# m2201-stereo-input.net
KiCad netlist of a schematic drawn in EAGLE
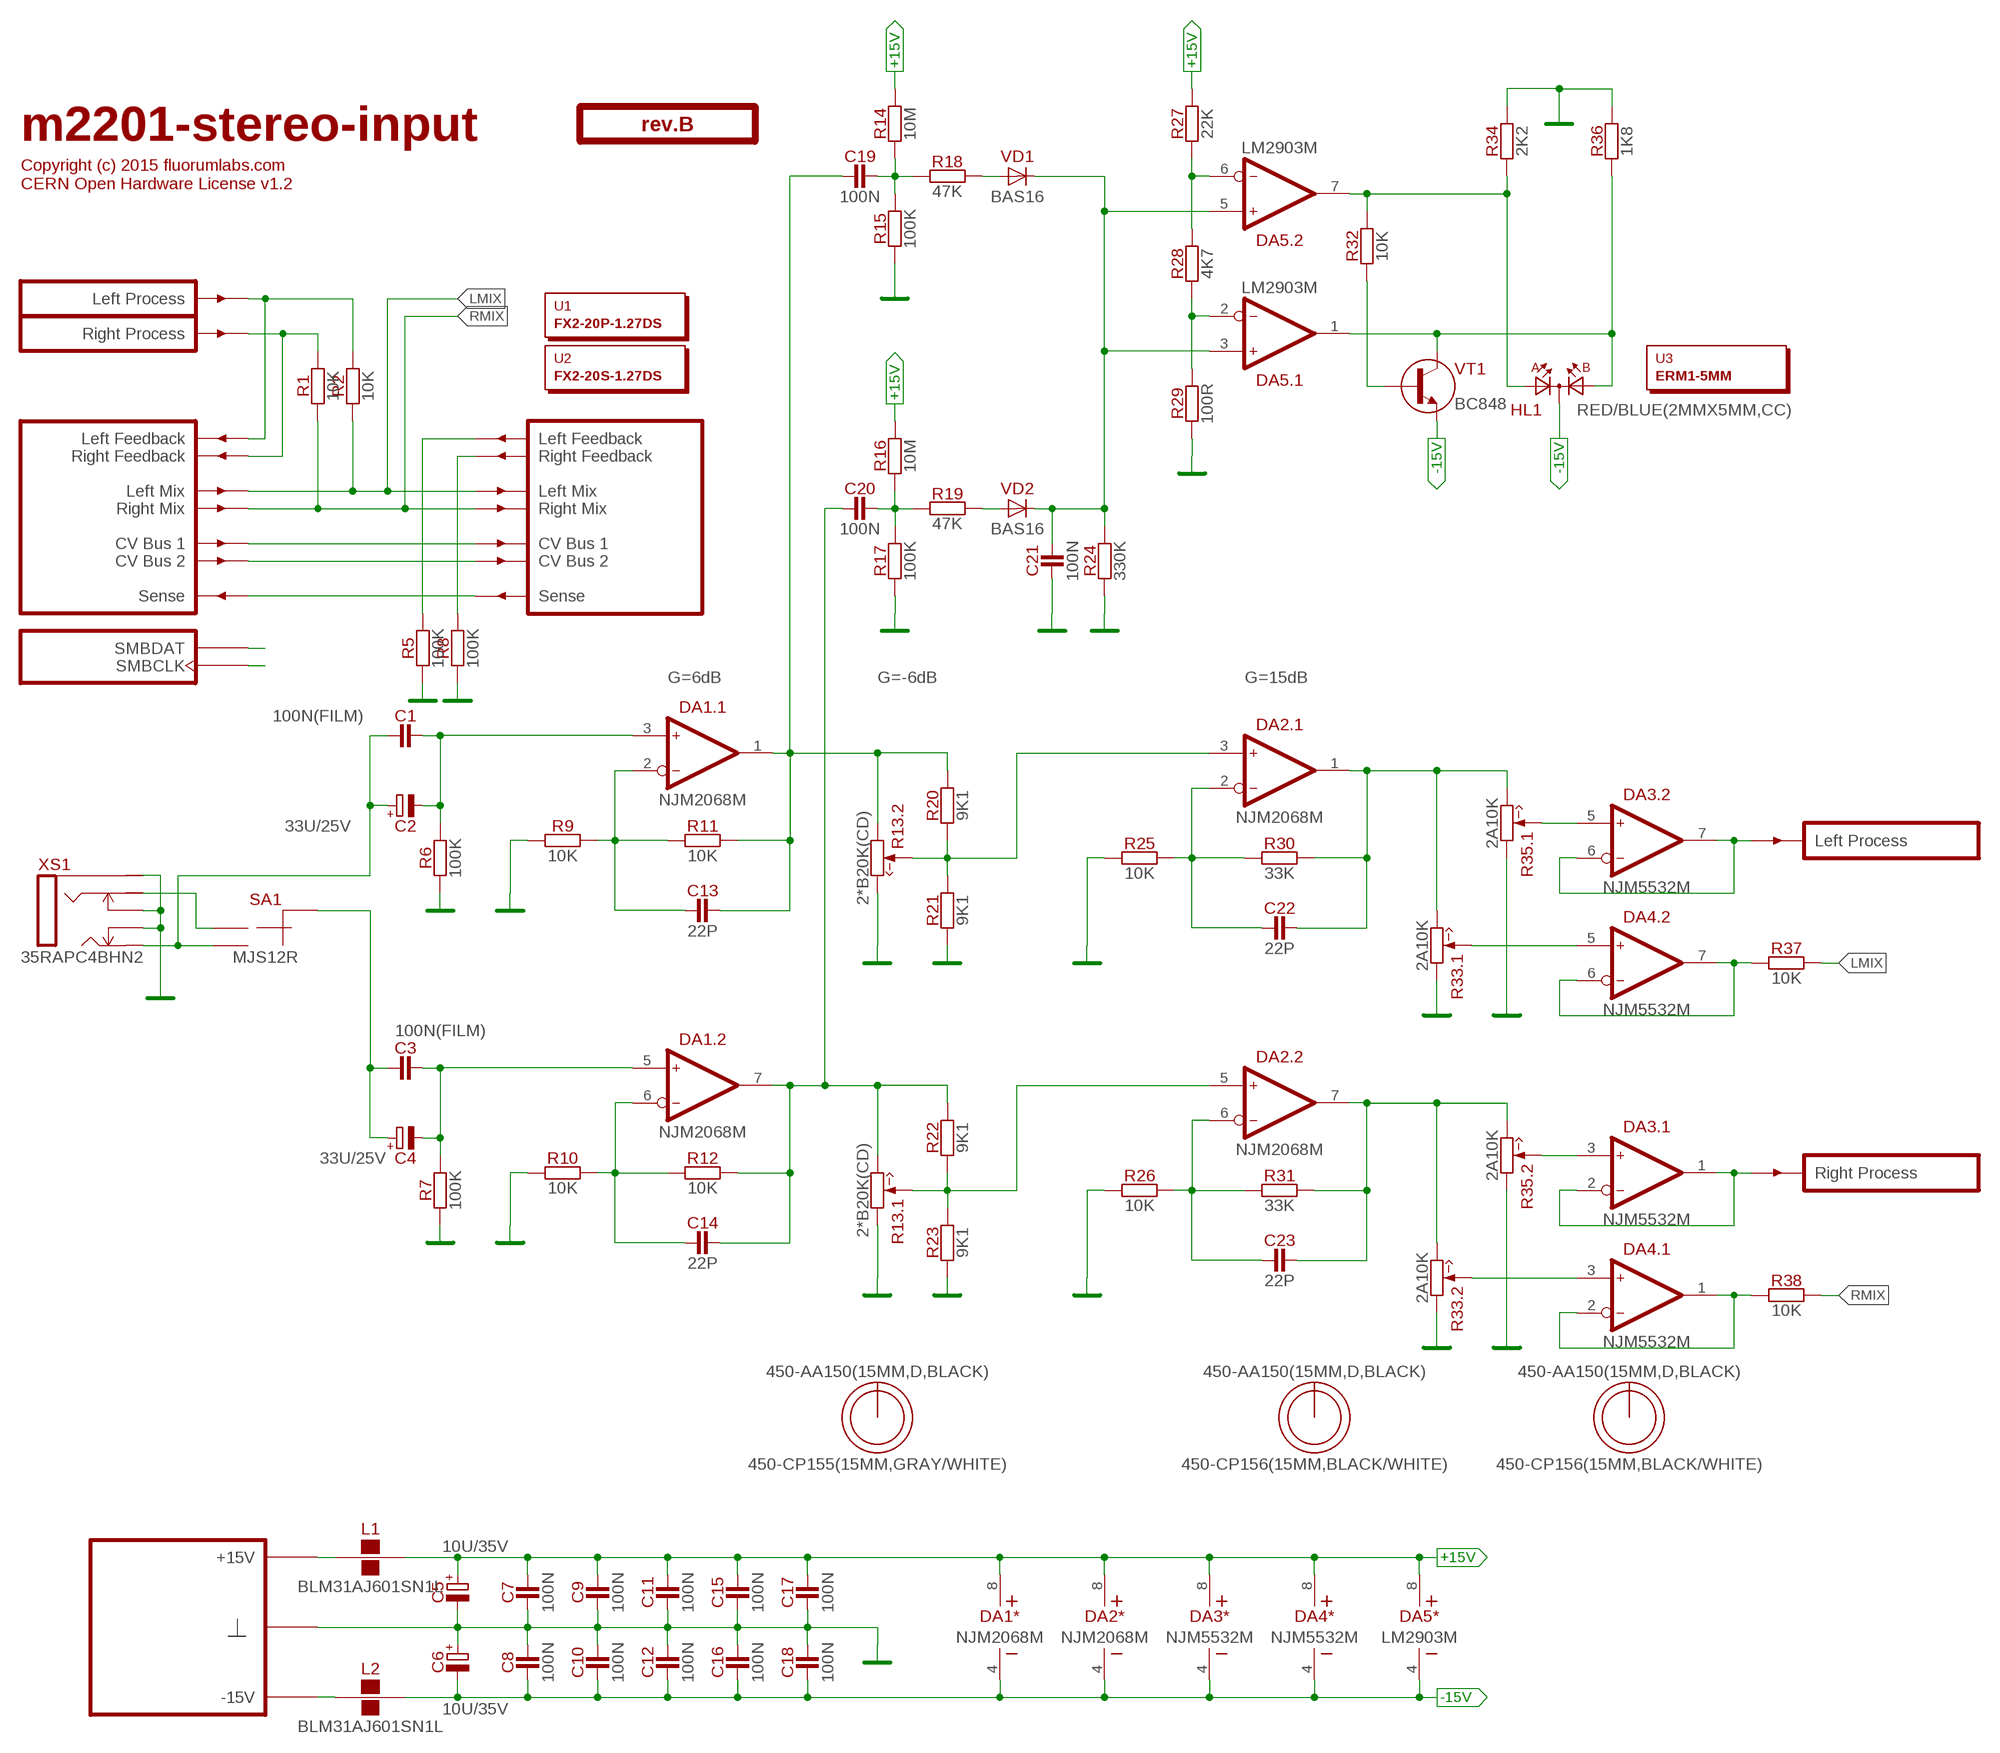
[diagram p0: schematic, sheet 1]

(export (version "E")
  (design (tool "Eeschema 10.0.6"))
  (components
    (comp (ref "C1")
      (value "100N(FILM)")
      (footprint "eagle-import:C050-025X075")
      (libsource (lib "eagle-import") (part "?100N(FILM)"))
    )
    (comp (ref "C2")
      (value "33U/25V")
      (footprint "eagle-import:E2,5-7")
      (libsource (lib "eagle-import") (part "?33U/25V"))
    )
    (comp (ref "C3")
      (value "100N(FILM)")
      (footprint "eagle-import:C050-025X075")
      (libsource (lib "eagle-import") (part "?100N(FILM)"))
    )
    (comp (ref "C4")
      (value "33U/25V")
      (footprint "eagle-import:E2,5-7")
      (libsource (lib "eagle-import") (part "?33U/25V"))
    )
    (comp (ref "C5")
      (value "10U/35V")
      (footprint "eagle-import:E2-5")
      (libsource (lib "eagle-import") (part "?10U/35V"))
    )
    (comp (ref "C6")
      (value "10U/35V")
      (footprint "eagle-import:E2-5")
      (libsource (lib "eagle-import") (part "?10U/35V"))
    )
    (comp (ref "C7")
      (value "100N")
      (footprint "eagle-import:C-0805")
      (libsource (lib "eagle-import") (part "?100N"))
    )
    (comp (ref "C8")
      (value "100N")
      (footprint "eagle-import:C-0805")
      (libsource (lib "eagle-import") (part "?100N"))
    )
    (comp (ref "C9")
      (value "100N")
      (footprint "eagle-import:C-0805")
      (libsource (lib "eagle-import") (part "?100N"))
    )
    (comp (ref "C10")
      (value "100N")
      (footprint "eagle-import:C-0805")
      (libsource (lib "eagle-import") (part "?100N"))
    )
    (comp (ref "C11")
      (value "100N")
      (footprint "eagle-import:C-0805")
      (libsource (lib "eagle-import") (part "?100N"))
    )
    (comp (ref "C12")
      (value "100N")
      (footprint "eagle-import:C-0805")
      (libsource (lib "eagle-import") (part "?100N"))
    )
    (comp (ref "C13")
      (value "22P")
      (footprint "eagle-import:C-0805")
      (libsource (lib "eagle-import") (part "?22P"))
    )
    (comp (ref "C14")
      (value "22P")
      (footprint "eagle-import:C-0805")
      (libsource (lib "eagle-import") (part "?22P"))
    )
    (comp (ref "C15")
      (value "100N")
      (footprint "eagle-import:C-0805")
      (libsource (lib "eagle-import") (part "?100N"))
    )
    (comp (ref "C16")
      (value "100N")
      (footprint "eagle-import:C-0805")
      (libsource (lib "eagle-import") (part "?100N"))
    )
    (comp (ref "C17")
      (value "100N")
      (footprint "eagle-import:C-0805")
      (libsource (lib "eagle-import") (part "?100N"))
    )
    (comp (ref "C18")
      (value "100N")
      (footprint "eagle-import:C-0805")
      (libsource (lib "eagle-import") (part "?100N"))
    )
    (comp (ref "C19")
      (value "100N")
      (footprint "eagle-import:C-0805")
      (libsource (lib "eagle-import") (part "?100N"))
    )
    (comp (ref "C20")
      (value "100N")
      (footprint "eagle-import:C-0805")
      (libsource (lib "eagle-import") (part "?100N"))
    )
    (comp (ref "C21")
      (value "100N")
      (footprint "eagle-import:C-0805")
      (libsource (lib "eagle-import") (part "?100N"))
    )
    (comp (ref "C22")
      (value "22P")
      (footprint "eagle-import:C-0805")
      (libsource (lib "eagle-import") (part "?22P"))
    )
    (comp (ref "C23")
      (value "22P")
      (footprint "eagle-import:C-0805")
      (libsource (lib "eagle-import") (part "?22P"))
    )
    (comp (ref "DA1")
      (value "NJM2068M")
      (footprint "eagle-import:SO-8")
      (libsource (lib "eagle-import") (part "NJM2068M"))
    )
    (comp (ref "DA2")
      (value "NJM2068M")
      (footprint "eagle-import:SO-8")
      (libsource (lib "eagle-import") (part "NJM2068M"))
    )
    (comp (ref "DA3")
      (value "NJM5532M")
      (footprint "eagle-import:SO-8")
      (libsource (lib "eagle-import") (part "NJM5532M"))
    )
    (comp (ref "DA4")
      (value "NJM5532M")
      (footprint "eagle-import:SO-8")
      (libsource (lib "eagle-import") (part "NJM5532M"))
    )
    (comp (ref "DA5")
      (value "LM2903M")
      (footprint "eagle-import:SO-8")
      (libsource (lib "eagle-import") (part "LM2903M"))
    )
    (comp (ref "HL1")
      (value "RED/BLUE(2MMX5MM,CC)")
      (footprint "eagle-import:LED2X5-3PIN")
      (libsource (lib "eagle-import") (part "?(2MMX5MM,CC)RED/BLUE"))
    )
    (comp (ref "L1")
      (value "BLM31AJ601SN1L")
      (footprint "eagle-import:1206")
      (libsource (lib "eagle-import") (part "BLM31AJ601SN1L"))
    )
    (comp (ref "L2")
      (value "BLM31AJ601SN1L")
      (footprint "eagle-import:1206")
      (libsource (lib "eagle-import") (part "BLM31AJ601SN1L"))
    )
    (comp (ref "O1")
      (value "TITLE")
      (footprint "eagle-import:EMPTY")
      (libsource (lib "eagle-import") (part "TITLE"))
    )
    (comp (ref "O2")
      (value "450-AA150(15MM,D,BLACK)")
      (footprint "eagle-import:EMPTY")
      (libsource (lib "eagle-import") (part "450-AA?150(15MM,D,BLACK)"))
    )
    (comp (ref "O3")
      (value "450-CP155(15MM,GRAY/WHITE)")
      (footprint "eagle-import:EMPTY")
      (libsource (lib "eagle-import") (part "450-C?P155(15MM,GRAY/WHITE)"))
    )
    (comp (ref "O4")
      (value "450-AA150(15MM,D,BLACK)")
      (footprint "eagle-import:EMPTY")
      (libsource (lib "eagle-import") (part "450-AA?150(15MM,D,BLACK)"))
    )
    (comp (ref "O5")
      (value "450-CP156(15MM,BLACK/WHITE)")
      (footprint "eagle-import:EMPTY")
      (libsource (lib "eagle-import") (part "450-C?P156(15MM,BLACK/WHITE)"))
    )
    (comp (ref "O6")
      (value "450-AA150(15MM,D,BLACK)")
      (footprint "eagle-import:EMPTY")
      (libsource (lib "eagle-import") (part "450-AA?150(15MM,D,BLACK)"))
    )
    (comp (ref "O7")
      (value "450-CP156(15MM,BLACK/WHITE)")
      (footprint "eagle-import:EMPTY")
      (libsource (lib "eagle-import") (part "450-C?P156(15MM,BLACK/WHITE)"))
    )
    (comp (ref "PCB1")
      (value "rev.B")
      (footprint "eagle-import:ST2-BOARD-50")
      (libsource (lib "eagle-import") (part "ST2-BOARD-50"))
    )
    (comp (ref "R1")
      (value "10K")
      (footprint "eagle-import:R-0805")
      (libsource (lib "eagle-import") (part "?10K"))
    )
    (comp (ref "R2")
      (value "10K")
      (footprint "eagle-import:R-0805")
      (libsource (lib "eagle-import") (part "?10K"))
    )
    (comp (ref "R5")
      (value "100K")
      (footprint "eagle-import:R-0805")
      (libsource (lib "eagle-import") (part "?100K"))
    )
    (comp (ref "R6")
      (value "100K")
      (footprint "eagle-import:R-0805")
      (libsource (lib "eagle-import") (part "?100K"))
    )
    (comp (ref "R7")
      (value "100K")
      (footprint "eagle-import:R-0805")
      (libsource (lib "eagle-import") (part "?100K"))
    )
    (comp (ref "R8")
      (value "100K")
      (footprint "eagle-import:R-0805")
      (libsource (lib "eagle-import") (part "?100K"))
    )
    (comp (ref "R9")
      (value "10K")
      (footprint "eagle-import:R-0805")
      (libsource (lib "eagle-import") (part "?10K"))
    )
    (comp (ref "R10")
      (value "10K")
      (footprint "eagle-import:R-0805")
      (libsource (lib "eagle-import") (part "?10K"))
    )
    (comp (ref "R11")
      (value "10K")
      (footprint "eagle-import:R-0805")
      (libsource (lib "eagle-import") (part "?10K"))
    )
    (comp (ref "R12")
      (value "10K")
      (footprint "eagle-import:R-0805")
      (libsource (lib "eagle-import") (part "?10K"))
    )
    (comp (ref "R13")
      (value "2*B20K(CD)")
      (footprint "eagle-import:RV11-DUAL")
      (libsource (lib "eagle-import") (part "2?B20K(CD)"))
    )
    (comp (ref "R14")
      (value "10M")
      (footprint "eagle-import:R-0805")
      (libsource (lib "eagle-import") (part "?10M"))
    )
    (comp (ref "R15")
      (value "100K")
      (footprint "eagle-import:R-0805")
      (libsource (lib "eagle-import") (part "?100K"))
    )
    (comp (ref "R16")
      (value "10M")
      (footprint "eagle-import:R-0805")
      (libsource (lib "eagle-import") (part "?10M"))
    )
    (comp (ref "R17")
      (value "100K")
      (footprint "eagle-import:R-0805")
      (libsource (lib "eagle-import") (part "?100K"))
    )
    (comp (ref "R18")
      (value "47K")
      (footprint "eagle-import:R-0805")
      (libsource (lib "eagle-import") (part "?47K"))
    )
    (comp (ref "R19")
      (value "47K")
      (footprint "eagle-import:R-0805")
      (libsource (lib "eagle-import") (part "?47K"))
    )
    (comp (ref "R20")
      (value "9K1")
      (footprint "eagle-import:R-0805")
      (libsource (lib "eagle-import") (part "?9K1"))
    )
    (comp (ref "R21")
      (value "9K1")
      (footprint "eagle-import:R-0805")
      (libsource (lib "eagle-import") (part "?9K1"))
    )
    (comp (ref "R22")
      (value "9K1")
      (footprint "eagle-import:R-0805")
      (libsource (lib "eagle-import") (part "?9K1"))
    )
    (comp (ref "R23")
      (value "9K1")
      (footprint "eagle-import:R-0805")
      (libsource (lib "eagle-import") (part "?9K1"))
    )
    (comp (ref "R24")
      (value "330K")
      (footprint "eagle-import:R-0805")
      (libsource (lib "eagle-import") (part "?330K"))
    )
    (comp (ref "R25")
      (value "10K")
      (footprint "eagle-import:R-0805")
      (libsource (lib "eagle-import") (part "?10K"))
    )
    (comp (ref "R26")
      (value "10K")
      (footprint "eagle-import:R-0805")
      (libsource (lib "eagle-import") (part "?10K"))
    )
    (comp (ref "R27")
      (value "22K")
      (footprint "eagle-import:R-0805")
      (libsource (lib "eagle-import") (part "?22K"))
    )
    (comp (ref "R28")
      (value "4K7")
      (footprint "eagle-import:R-0805")
      (libsource (lib "eagle-import") (part "?4K7"))
    )
    (comp (ref "R29")
      (value "100R")
      (footprint "eagle-import:R-0805")
      (libsource (lib "eagle-import") (part "?100R"))
    )
    (comp (ref "R30")
      (value "33K")
      (footprint "eagle-import:R-0805")
      (libsource (lib "eagle-import") (part "?33K"))
    )
    (comp (ref "R31")
      (value "33K")
      (footprint "eagle-import:R-0805")
      (libsource (lib "eagle-import") (part "?33K"))
    )
    (comp (ref "R32")
      (value "10K")
      (footprint "eagle-import:R-0805")
      (libsource (lib "eagle-import") (part "?10K"))
    )
    (comp (ref "R33")
      (value "2A10K")
      (footprint "eagle-import:RV11-DUAL")
      (libsource (lib "eagle-import") (part "2?A10K"))
    )
    (comp (ref "R34")
      (value "2K2")
      (footprint "eagle-import:R-0805")
      (libsource (lib "eagle-import") (part "?2K2"))
    )
    (comp (ref "R35")
      (value "2A10K")
      (footprint "eagle-import:RV11-DUAL")
      (libsource (lib "eagle-import") (part "2?A10K"))
    )
    (comp (ref "R36")
      (value "1K8")
      (footprint "eagle-import:R-0805")
      (libsource (lib "eagle-import") (part "?1K8"))
    )
    (comp (ref "R37")
      (value "10K")
      (footprint "eagle-import:R-0805")
      (libsource (lib "eagle-import") (part "?10K"))
    )
    (comp (ref "R38")
      (value "10K")
      (footprint "eagle-import:R-0805")
      (libsource (lib "eagle-import") (part "?10K"))
    )
    (comp (ref "SA1")
      (value "MJS12R")
      (footprint "eagle-import:APEM-MJS12R")
      (libsource (lib "eagle-import") (part "MJS12R"))
    )
    (comp (ref "U1")
      (value "FX2-20P-1.27DS")
      (footprint "eagle-import:EMPTY")
      (libsource (lib "eagle-import") (part "?FX2-20P-1.27DS"))
    )
    (comp (ref "U2")
      (value "FX2-20S-1.27DS")
      (footprint "eagle-import:EMPTY")
      (libsource (lib "eagle-import") (part "?FX2-20S-1.27DS"))
    )
    (comp (ref "U3")
      (value "ERM1-5MM")
      (footprint "eagle-import:EMPTY")
      (libsource (lib "eagle-import") (part "?ERM1-5MM"))
    )
    (comp (ref "VD1")
      (value "BAS16")
      (footprint "eagle-import:SOT23")
      (libsource (lib "eagle-import") (part "?BAS16"))
    )
    (comp (ref "VD2")
      (value "BAS16")
      (footprint "eagle-import:SOT23")
      (libsource (lib "eagle-import") (part "?BAS16"))
    )
    (comp (ref "VT1")
      (value "BC848")
      (footprint "eagle-import:SOT23")
      (libsource (lib "eagle-import") (part "?BC848"))
    )
    (comp (ref "XS1")
      (value "35RAPC4BHN2")
      (footprint "eagle-import:35RAP")
      (libsource (lib "eagle-import") (part "35RAPC4BHN2"))
    )
  )
  (nets
    (net (code "1") (name "+15V") (class "Default")
      (node (ref "C11") (pin "2") (pinfunction "2_2") (pintype "passive"))
      (node (ref "C15") (pin "2") (pinfunction "2_2") (pintype "passive"))
      (node (ref "C17") (pin "2") (pinfunction "2_2") (pintype "passive"))
      (node (ref "C5") (pin "+") (pinfunction "+_+") (pintype "passive"))
      (node (ref "C7") (pin "2") (pinfunction "2_2") (pintype "passive"))
      (node (ref "C9") (pin "2") (pinfunction "2_2") (pintype "passive"))
      (node (ref "DA1") (pin "8") (pinfunction "V+_8") (pintype "power_in"))
      (node (ref "DA2") (pin "8") (pinfunction "V+_8") (pintype "power_in"))
      (node (ref "DA3") (pin "8") (pinfunction "V+_8") (pintype "power_in"))
      (node (ref "DA4") (pin "8") (pinfunction "V+_8") (pintype "power_in"))
      (node (ref "DA5") (pin "8") (pinfunction "V+_8") (pintype "power_in"))
      (node (ref "L1") (pin "2") (pinfunction "2_2") (pintype "passive"))
      (node (ref "R14") (pin "2") (pinfunction "2_2") (pintype "passive"))
      (node (ref "R16") (pin "2") (pinfunction "2_2") (pintype "passive"))
      (node (ref "R27") (pin "2") (pinfunction "2_2") (pintype "passive"))
    )
    (net (code "2") (name "-15V") (class "Default")
      (node (ref "C10") (pin "1") (pinfunction "1_1") (pintype "passive"))
      (node (ref "C12") (pin "1") (pinfunction "1_1") (pintype "passive"))
      (node (ref "C16") (pin "1") (pinfunction "1_1") (pintype "passive"))
      (node (ref "C18") (pin "1") (pinfunction "1_1") (pintype "passive"))
      (node (ref "C6") (pin "-") (pinfunction "-_-") (pintype "passive"))
      (node (ref "C8") (pin "1") (pinfunction "1_1") (pintype "passive"))
      (node (ref "DA1") (pin "4") (pinfunction "V-_4") (pintype "power_in"))
      (node (ref "DA2") (pin "4") (pinfunction "V-_4") (pintype "power_in"))
      (node (ref "DA3") (pin "4") (pinfunction "V-_4") (pintype "power_in"))
      (node (ref "DA4") (pin "4") (pinfunction "V-_4") (pintype "power_in"))
      (node (ref "DA5") (pin "4") (pinfunction "V-_4") (pintype "power_in"))
      (node (ref "HL1") (pin "K") (pinfunction "K_K") (pintype "passive"))
      (node (ref "L2") (pin "2") (pinfunction "2_2") (pintype "passive"))
      (node (ref "VT1") (pin "2") (pinfunction "E_2") (pintype "passive"))
    )
    (net (code "3") (name "GND") (class "Default")
      (node (ref "C10") (pin "2") (pinfunction "2_2") (pintype "passive"))
      (node (ref "C11") (pin "1") (pinfunction "1_1") (pintype "passive"))
      (node (ref "C12") (pin "2") (pinfunction "2_2") (pintype "passive"))
      (node (ref "C15") (pin "1") (pinfunction "1_1") (pintype "passive"))
      (node (ref "C16") (pin "2") (pinfunction "2_2") (pintype "passive"))
      (node (ref "C17") (pin "1") (pinfunction "1_1") (pintype "passive"))
      (node (ref "C18") (pin "2") (pinfunction "2_2") (pintype "passive"))
      (node (ref "C21") (pin "1") (pinfunction "1_1") (pintype "passive"))
      (node (ref "C5") (pin "-") (pinfunction "-_-") (pintype "passive"))
      (node (ref "C6") (pin "+") (pinfunction "+_+") (pintype "passive"))
      (node (ref "C7") (pin "1") (pinfunction "1_1") (pintype "passive"))
      (node (ref "C8") (pin "2") (pinfunction "2_2") (pintype "passive"))
      (node (ref "C9") (pin "1") (pinfunction "1_1") (pintype "passive"))
      (node (ref "PCB1") (pin "B4") (pinfunction "GND_B4") (pintype "bidirectional"))
      (node (ref "PCB1") (pin "B4'") (pinfunction "GND_B4'") (pintype "bidirectional"))
      (node (ref "PCB1") (pin "B5") (pinfunction "GND_B5") (pintype "bidirectional"))
      (node (ref "PCB1") (pin "B5'") (pinfunction "GND_B5'") (pintype "bidirectional"))
      (node (ref "PCB1") (pin "B6") (pinfunction "GND_B6") (pintype "bidirectional"))
      (node (ref "PCB1") (pin "B6'") (pinfunction "GND_B6'") (pintype "bidirectional"))
      (node (ref "PCB1") (pin "B7") (pinfunction "GND_B7") (pintype "bidirectional"))
      (node (ref "PCB1") (pin "B7'") (pinfunction "GND_B7'") (pintype "bidirectional"))
      (node (ref "PCB1") (pin "B8") (pinfunction "GND_B8") (pintype "bidirectional"))
      (node (ref "PCB1") (pin "B8'") (pinfunction "GND_B8'") (pintype "bidirectional"))
      (node (ref "R10") (pin "1") (pinfunction "1_1") (pintype "passive"))
      (node (ref "R13") (pin "1") (pinfunction "CCW_1") (pintype "passive"))
      (node (ref "R13") (pin "3'") (pinfunction "CW_3'") (pintype "passive"))
      (node (ref "R15") (pin "1") (pinfunction "1_1") (pintype "passive"))
      (node (ref "R17") (pin "1") (pinfunction "1_1") (pintype "passive"))
      (node (ref "R21") (pin "1") (pinfunction "1_1") (pintype "passive"))
      (node (ref "R23") (pin "1") (pinfunction "1_1") (pintype "passive"))
      (node (ref "R24") (pin "1") (pinfunction "1_1") (pintype "passive"))
      (node (ref "R25") (pin "1") (pinfunction "1_1") (pintype "passive"))
      (node (ref "R26") (pin "1") (pinfunction "1_1") (pintype "passive"))
      (node (ref "R29") (pin "1") (pinfunction "1_1") (pintype "passive"))
      (node (ref "R33") (pin "1") (pinfunction "CCW_1") (pintype "passive"))
      (node (ref "R33") (pin "1'") (pinfunction "CCW_1'") (pintype "passive"))
      (node (ref "R34") (pin "2") (pinfunction "2_2") (pintype "passive"))
      (node (ref "R35") (pin "1") (pinfunction "CCW_1") (pintype "passive"))
      (node (ref "R35") (pin "1'") (pinfunction "CCW_1'") (pintype "passive"))
      (node (ref "R36") (pin "2") (pinfunction "2_2") (pintype "passive"))
      (node (ref "R5") (pin "1") (pinfunction "1_1") (pintype "passive"))
      (node (ref "R6") (pin "1") (pinfunction "1_1") (pintype "passive"))
      (node (ref "R7") (pin "1") (pinfunction "1_1") (pintype "passive"))
      (node (ref "R8") (pin "1") (pinfunction "1_1") (pintype "passive"))
      (node (ref "R9") (pin "1") (pinfunction "1_1") (pintype "passive"))
      (node (ref "XS1") (pin "1") (pinfunction "S_1") (pintype "passive"))
      (node (ref "XS1") (pin "10") (pinfunction "TN_10") (pintype "passive"))
      (node (ref "XS1") (pin "11") (pinfunction "RN_11") (pintype "passive"))
    )
    (net (code "4") (name "LMIX") (class "Default")
      (node (ref "PCB1") (pin "ALMIX") (pinfunction "LMIX_ALMIX") (pintype "bidirectional"))
      (node (ref "PCB1") (pin "ALMIX'") (pinfunction "LMIX'_ALMIX'") (pintype "bidirectional"))
      (node (ref "R2") (pin "1") (pinfunction "1_1") (pintype "passive"))
      (node (ref "R37") (pin "2") (pinfunction "2_2") (pintype "passive"))
    )
    (net (code "5") (name "Net-(C19-Pad2)") (class "Default")
      (node (ref "C19") (pin "2") (pinfunction "2_2") (pintype "passive"))
      (node (ref "R14") (pin "1") (pinfunction "1_1") (pintype "passive"))
      (node (ref "R15") (pin "2") (pinfunction "2_2") (pintype "passive"))
      (node (ref "R18") (pin "1") (pinfunction "1_1") (pintype "passive"))
    )
    (net (code "6") (name "Net-(C20-Pad2)") (class "Default")
      (node (ref "C20") (pin "2") (pinfunction "2_2") (pintype "passive"))
      (node (ref "R16") (pin "1") (pinfunction "1_1") (pintype "passive"))
      (node (ref "R17") (pin "2") (pinfunction "2_2") (pintype "passive"))
      (node (ref "R19") (pin "1") (pinfunction "1_1") (pintype "passive"))
    )
    (net (code "7") (name "Net-(DA1B-IN+)") (class "Default")
      (node (ref "C1") (pin "2") (pinfunction "2_2") (pintype "passive"))
      (node (ref "C2") (pin "-") (pinfunction "-_-") (pintype "passive"))
      (node (ref "DA1") (pin "3") (pinfunction "IN+_3") (pintype "input"))
      (node (ref "R6") (pin "2") (pinfunction "2_2") (pintype "passive"))
    )
    (net (code "8") (name "Net-(DA1B-IN-)") (class "Default")
      (node (ref "C13") (pin "1") (pinfunction "1_1") (pintype "passive"))
      (node (ref "DA1") (pin "2") (pinfunction "IN-_2") (pintype "input"))
      (node (ref "R11") (pin "1") (pinfunction "1_1") (pintype "passive"))
      (node (ref "R9") (pin "2") (pinfunction "2_2") (pintype "passive"))
    )
    (net (code "9") (name "Net-(DA1B-OUT)") (class "Default")
      (node (ref "C13") (pin "2") (pinfunction "2_2") (pintype "passive"))
      (node (ref "C19") (pin "1") (pinfunction "1_1") (pintype "passive"))
      (node (ref "DA1") (pin "1") (pinfunction "OUT_1") (pintype "output"))
      (node (ref "R11") (pin "2") (pinfunction "2_2") (pintype "passive"))
      (node (ref "R13") (pin "1'") (pinfunction "CCW_1'") (pintype "passive"))
      (node (ref "R20") (pin "2") (pinfunction "2_2") (pintype "passive"))
    )
    (net (code "10") (name "Net-(DA1C-IN+)") (class "Default")
      (node (ref "C3") (pin "2") (pinfunction "2_2") (pintype "passive"))
      (node (ref "C4") (pin "-") (pinfunction "-_-") (pintype "passive"))
      (node (ref "DA1") (pin "5") (pinfunction "IN+_5") (pintype "input"))
      (node (ref "R7") (pin "2") (pinfunction "2_2") (pintype "passive"))
    )
    (net (code "11") (name "Net-(DA1C-IN-)") (class "Default")
      (node (ref "C14") (pin "1") (pinfunction "1_1") (pintype "passive"))
      (node (ref "DA1") (pin "6") (pinfunction "IN-_6") (pintype "input"))
      (node (ref "R10") (pin "2") (pinfunction "2_2") (pintype "passive"))
      (node (ref "R12") (pin "1") (pinfunction "1_1") (pintype "passive"))
    )
    (net (code "12") (name "Net-(DA1C-OUT)") (class "Default")
      (node (ref "C14") (pin "2") (pinfunction "2_2") (pintype "passive"))
      (node (ref "C20") (pin "1") (pinfunction "1_1") (pintype "passive"))
      (node (ref "DA1") (pin "7") (pinfunction "OUT_7") (pintype "output"))
      (node (ref "R12") (pin "2") (pinfunction "2_2") (pintype "passive"))
      (node (ref "R13") (pin "3") (pinfunction "CW_3") (pintype "passive"))
      (node (ref "R22") (pin "2") (pinfunction "2_2") (pintype "passive"))
    )
    (net (code "13") (name "Net-(DA2B-IN+)") (class "Default")
      (node (ref "DA2") (pin "3") (pinfunction "IN+_3") (pintype "input"))
      (node (ref "R13") (pin "2'") (pinfunction "W_2'") (pintype "passive"))
      (node (ref "R20") (pin "1") (pinfunction "1_1") (pintype "passive"))
      (node (ref "R21") (pin "2") (pinfunction "2_2") (pintype "passive"))
    )
    (net (code "14") (name "Net-(DA2B-IN-)") (class "Default")
      (node (ref "C22") (pin "1") (pinfunction "1_1") (pintype "passive"))
      (node (ref "DA2") (pin "2") (pinfunction "IN-_2") (pintype "input"))
      (node (ref "R25") (pin "2") (pinfunction "2_2") (pintype "passive"))
      (node (ref "R30") (pin "1") (pinfunction "1_1") (pintype "passive"))
    )
    (net (code "15") (name "Net-(DA2B-OUT)") (class "Default")
      (node (ref "C22") (pin "2") (pinfunction "2_2") (pintype "passive"))
      (node (ref "DA2") (pin "1") (pinfunction "OUT_1") (pintype "output"))
      (node (ref "R30") (pin "2") (pinfunction "2_2") (pintype "passive"))
      (node (ref "R33") (pin "3") (pinfunction "CW_3") (pintype "passive"))
      (node (ref "R35") (pin "3") (pinfunction "CW_3") (pintype "passive"))
    )
    (net (code "16") (name "Net-(DA2C-IN+)") (class "Default")
      (node (ref "DA2") (pin "5") (pinfunction "IN+_5") (pintype "input"))
      (node (ref "R13") (pin "2") (pinfunction "W_2") (pintype "passive"))
      (node (ref "R22") (pin "1") (pinfunction "1_1") (pintype "passive"))
      (node (ref "R23") (pin "2") (pinfunction "2_2") (pintype "passive"))
    )
    (net (code "17") (name "Net-(DA2C-IN-)") (class "Default")
      (node (ref "C23") (pin "1") (pinfunction "1_1") (pintype "passive"))
      (node (ref "DA2") (pin "6") (pinfunction "IN-_6") (pintype "input"))
      (node (ref "R26") (pin "2") (pinfunction "2_2") (pintype "passive"))
      (node (ref "R31") (pin "1") (pinfunction "1_1") (pintype "passive"))
    )
    (net (code "18") (name "Net-(DA2C-OUT)") (class "Default")
      (node (ref "C23") (pin "2") (pinfunction "2_2") (pintype "passive"))
      (node (ref "DA2") (pin "7") (pinfunction "OUT_7") (pintype "output"))
      (node (ref "R31") (pin "2") (pinfunction "2_2") (pintype "passive"))
      (node (ref "R33") (pin "3'") (pinfunction "CW_3'") (pintype "passive"))
      (node (ref "R35") (pin "3'") (pinfunction "CW_3'") (pintype "passive"))
    )
    (net (code "19") (name "Net-(DA3B-IN+)") (class "Default")
      (node (ref "DA3") (pin "3") (pinfunction "IN+_3") (pintype "input"))
      (node (ref "R35") (pin "2'") (pinfunction "W_2'") (pintype "passive"))
    )
    (net (code "20") (name "Net-(DA3B-IN-)") (class "Default")
      (node (ref "DA3") (pin "1") (pinfunction "OUT_1") (pintype "output"))
      (node (ref "DA3") (pin "2") (pinfunction "IN-_2") (pintype "input"))
      (node (ref "PCB1") (pin "BOUTR'") (pinfunction "OUTR_BOUTR'") (pintype "bidirectional"))
    )
    (net (code "21") (name "Net-(DA3C-IN+)") (class "Default")
      (node (ref "DA3") (pin "5") (pinfunction "IN+_5") (pintype "input"))
      (node (ref "R35") (pin "2") (pinfunction "W_2") (pintype "passive"))
    )
    (net (code "22") (name "Net-(DA3C-IN-)") (class "Default")
      (node (ref "DA3") (pin "6") (pinfunction "IN-_6") (pintype "input"))
      (node (ref "DA3") (pin "7") (pinfunction "OUT_7") (pintype "output"))
      (node (ref "PCB1") (pin "BOUTL'") (pinfunction "OUTL_BOUTL'") (pintype "bidirectional"))
    )
    (net (code "23") (name "Net-(DA4B-IN+)") (class "Default")
      (node (ref "DA4") (pin "3") (pinfunction "IN+_3") (pintype "input"))
      (node (ref "R33") (pin "2'") (pinfunction "W_2'") (pintype "passive"))
    )
    (net (code "24") (name "Net-(DA4B-IN-)") (class "Default")
      (node (ref "DA4") (pin "1") (pinfunction "OUT_1") (pintype "output"))
      (node (ref "DA4") (pin "2") (pinfunction "IN-_2") (pintype "input"))
      (node (ref "R38") (pin "1") (pinfunction "1_1") (pintype "passive"))
    )
    (net (code "25") (name "Net-(DA4C-IN+)") (class "Default")
      (node (ref "DA4") (pin "5") (pinfunction "IN+_5") (pintype "input"))
      (node (ref "R33") (pin "2") (pinfunction "W_2") (pintype "passive"))
    )
    (net (code "26") (name "Net-(DA4C-IN-)") (class "Default")
      (node (ref "DA4") (pin "6") (pinfunction "IN-_6") (pintype "input"))
      (node (ref "DA4") (pin "7") (pinfunction "OUT_7") (pintype "output"))
      (node (ref "R37") (pin "1") (pinfunction "1_1") (pintype "passive"))
    )
    (net (code "27") (name "Net-(DA5B-IN+)") (class "Default")
      (node (ref "C21") (pin "2") (pinfunction "2_2") (pintype "passive"))
      (node (ref "DA5") (pin "3") (pinfunction "IN+_3") (pintype "input"))
      (node (ref "DA5") (pin "5") (pinfunction "IN+_5") (pintype "input"))
      (node (ref "R24") (pin "2") (pinfunction "2_2") (pintype "passive"))
      (node (ref "VD1") (pin "2") (pinfunction "C_2") (pintype "passive"))
      (node (ref "VD2") (pin "2") (pinfunction "C_2") (pintype "passive"))
    )
    (net (code "28") (name "Net-(DA5B-IN-)") (class "Default")
      (node (ref "DA5") (pin "2") (pinfunction "IN-_2") (pintype "input"))
      (node (ref "R28") (pin "1") (pinfunction "1_1") (pintype "passive"))
      (node (ref "R29") (pin "2") (pinfunction "2_2") (pintype "passive"))
    )
    (net (code "29") (name "Net-(DA5B-OUT)") (class "Default")
      (node (ref "DA5") (pin "1") (pinfunction "OUT_1") (pintype "output"))
      (node (ref "HL1") (pin "A2") (pinfunction "A2_A2") (pintype "passive"))
      (node (ref "R36") (pin "1") (pinfunction "1_1") (pintype "passive"))
      (node (ref "VT1") (pin "3") (pinfunction "C_3") (pintype "passive"))
    )
    (net (code "30") (name "Net-(DA5C-IN-)") (class "Default")
      (node (ref "DA5") (pin "6") (pinfunction "IN-_6") (pintype "input"))
      (node (ref "R27") (pin "1") (pinfunction "1_1") (pintype "passive"))
      (node (ref "R28") (pin "2") (pinfunction "2_2") (pintype "passive"))
    )
    (net (code "31") (name "Net-(DA5C-OUT)") (class "Default")
      (node (ref "DA5") (pin "7") (pinfunction "OUT_7") (pintype "output"))
      (node (ref "HL1") (pin "A1") (pinfunction "A1_A1") (pintype "passive"))
      (node (ref "R32") (pin "2") (pinfunction "2_2") (pintype "passive"))
      (node (ref "R34") (pin "1") (pinfunction "1_1") (pintype "passive"))
    )
    (net (code "32") (name "Net-(L1-Pad1)") (class "Default")
      (node (ref "L1") (pin "1") (pinfunction "1_1") (pintype "passive"))
      (node (ref "PCB1") (pin "A+15") (pinfunction "P+15V_A+15") (pintype "bidirectional"))
      (node (ref "PCB1") (pin "A+15'") (pinfunction "P+15V_A+15'") (pintype "bidirectional"))
      (node (ref "PCB1") (pin "B+15") (pinfunction "P+15V_B+15") (pintype "bidirectional"))
      (node (ref "PCB1") (pin "B+15'") (pinfunction "P+15V_B+15'") (pintype "bidirectional"))
    )
    (net (code "33") (name "Net-(L2-Pad1)") (class "Default")
      (node (ref "L2") (pin "1") (pinfunction "1_1") (pintype "passive"))
      (node (ref "PCB1") (pin "A-15") (pinfunction "P-15V_A-15") (pintype "bidirectional"))
      (node (ref "PCB1") (pin "A-15'") (pinfunction "P-15V_A-15'") (pintype "bidirectional"))
      (node (ref "PCB1") (pin "B-15") (pinfunction "P-15V_B-15") (pintype "bidirectional"))
      (node (ref "PCB1") (pin "B-15'") (pinfunction "P-15V_B-15'") (pintype "bidirectional"))
    )
    (net (code "34") (name "Net-(PCB1B-INL)") (class "Default")
      (node (ref "PCB1") (pin "ALFBK") (pinfunction "LFBK_ALFBK") (pintype "bidirectional"))
      (node (ref "PCB1") (pin "BINL") (pinfunction "INL_BINL") (pintype "bidirectional"))
      (node (ref "R2") (pin "2") (pinfunction "2_2") (pintype "passive"))
    )
    (net (code "35") (name "Net-(PCB1C-INR)") (class "Default")
      (node (ref "PCB1") (pin "ARFBK") (pinfunction "RFBK_ARFBK") (pintype "bidirectional"))
      (node (ref "PCB1") (pin "BINR") (pinfunction "INR_BINR") (pintype "bidirectional"))
      (node (ref "R1") (pin "2") (pinfunction "2_2") (pintype "passive"))
    )
    (net (code "36") (name "Net-(PCB1F-CV1)") (class "Default")
      (node (ref "PCB1") (pin "ACV1") (pinfunction "CV1_ACV1") (pintype "bidirectional"))
      (node (ref "PCB1") (pin "ACV1'") (pinfunction "CV1'_ACV1'") (pintype "bidirectional"))
    )
    (net (code "37") (name "Net-(PCB1F-CV2)") (class "Default")
      (node (ref "PCB1") (pin "ACV2") (pinfunction "CV2_ACV2") (pintype "bidirectional"))
      (node (ref "PCB1") (pin "ACV2'") (pinfunction "CV2'_ACV2'") (pintype "bidirectional"))
    )
    (net (code "38") (name "Net-(PCB1F-SENSE)") (class "Default")
      (node (ref "PCB1") (pin "BSENSE") (pinfunction "SENSE_BSENSE") (pintype "bidirectional"))
      (node (ref "PCB1") (pin "BSENSE'") (pinfunction "SENSE'_BSENSE'") (pintype "bidirectional"))
    )
    (net (code "39") (name "Net-(PCB1G-LFBK')") (class "Default")
      (node (ref "PCB1") (pin "ALFBK'") (pinfunction "LFBK'_ALFBK'") (pintype "bidirectional"))
      (node (ref "R5") (pin "2") (pinfunction "2_2") (pintype "passive"))
    )
    (net (code "40") (name "Net-(PCB1G-RFBK')") (class "Default")
      (node (ref "PCB1") (pin "ARFBK'") (pinfunction "RFBK'_ARFBK'") (pintype "bidirectional"))
      (node (ref "R8") (pin "2") (pinfunction "2_2") (pintype "passive"))
    )
    (net (code "41") (name "Net-(PCB1H-SMBCLK-PadASMBCLK')") (class "Default")
      (node (ref "PCB1") (pin "ASMBCLK") (pinfunction "SMBCLK_ASMBCLK") (pintype "bidirectional"))
      (node (ref "PCB1") (pin "ASMBCLK'") (pinfunction "SMBCLK_ASMBCLK'") (pintype "bidirectional"))
    )
    (net (code "42") (name "Net-(PCB1H-SMBDAT-PadASMBDAT')") (class "Default")
      (node (ref "PCB1") (pin "ASMBDAT") (pinfunction "SMBDAT_ASMBDAT") (pintype "bidirectional"))
      (node (ref "PCB1") (pin "ASMBDAT'") (pinfunction "SMBDAT_ASMBDAT'") (pintype "bidirectional"))
    )
    (net (code "43") (name "Net-(SA1-1)") (class "Default")
      (node (ref "SA1") (pin "NC") (pinfunction "1_NC") (pintype "passive"))
      (node (ref "XS1") (pin "3") (pinfunction "R_3") (pintype "passive"))
    )
    (net (code "44") (name "Net-(SA1-2)") (class "Default")
      (node (ref "C1") (pin "1") (pinfunction "1_1") (pintype "passive"))
      (node (ref "C2") (pin "+") (pinfunction "+_+") (pintype "passive"))
      (node (ref "SA1") (pin "NO") (pinfunction "2_NO") (pintype "passive"))
      (node (ref "XS1") (pin "2") (pinfunction "T_2") (pintype "passive"))
    )
    (net (code "45") (name "Net-(SA1-CM)") (class "Default")
      (node (ref "C3") (pin "1") (pinfunction "1_1") (pintype "passive"))
      (node (ref "C4") (pin "+") (pinfunction "+_+") (pintype "passive"))
      (node (ref "SA1") (pin "C") (pinfunction "CM_C") (pintype "passive"))
    )
    (net (code "46") (name "Net-(VD1-A)") (class "Default")
      (node (ref "R18") (pin "2") (pinfunction "2_2") (pintype "passive"))
      (node (ref "VD1") (pin "1") (pinfunction "A_1") (pintype "passive"))
    )
    (net (code "47") (name "Net-(VD2-A)") (class "Default")
      (node (ref "R19") (pin "2") (pinfunction "2_2") (pintype "passive"))
      (node (ref "VD2") (pin "1") (pinfunction "A_1") (pintype "passive"))
    )
    (net (code "48") (name "Net-(VT1-B)") (class "Default")
      (node (ref "R32") (pin "1") (pinfunction "1_1") (pintype "passive"))
      (node (ref "VT1") (pin "1") (pinfunction "B_1") (pintype "passive"))
    )
    (net (code "49") (name "RMIX") (class "Default")
      (node (ref "PCB1") (pin "ARMIX") (pinfunction "RMIX_ARMIX") (pintype "bidirectional"))
      (node (ref "PCB1") (pin "ARMIX'") (pinfunction "RMIX'_ARMIX'") (pintype "bidirectional"))
      (node (ref "R1") (pin "1") (pinfunction "1_1") (pintype "passive"))
      (node (ref "R38") (pin "2") (pinfunction "2_2") (pintype "passive"))
    )
  )
)
